# Course.net
KiCad netlist of a schematic drawn in Altium Designer
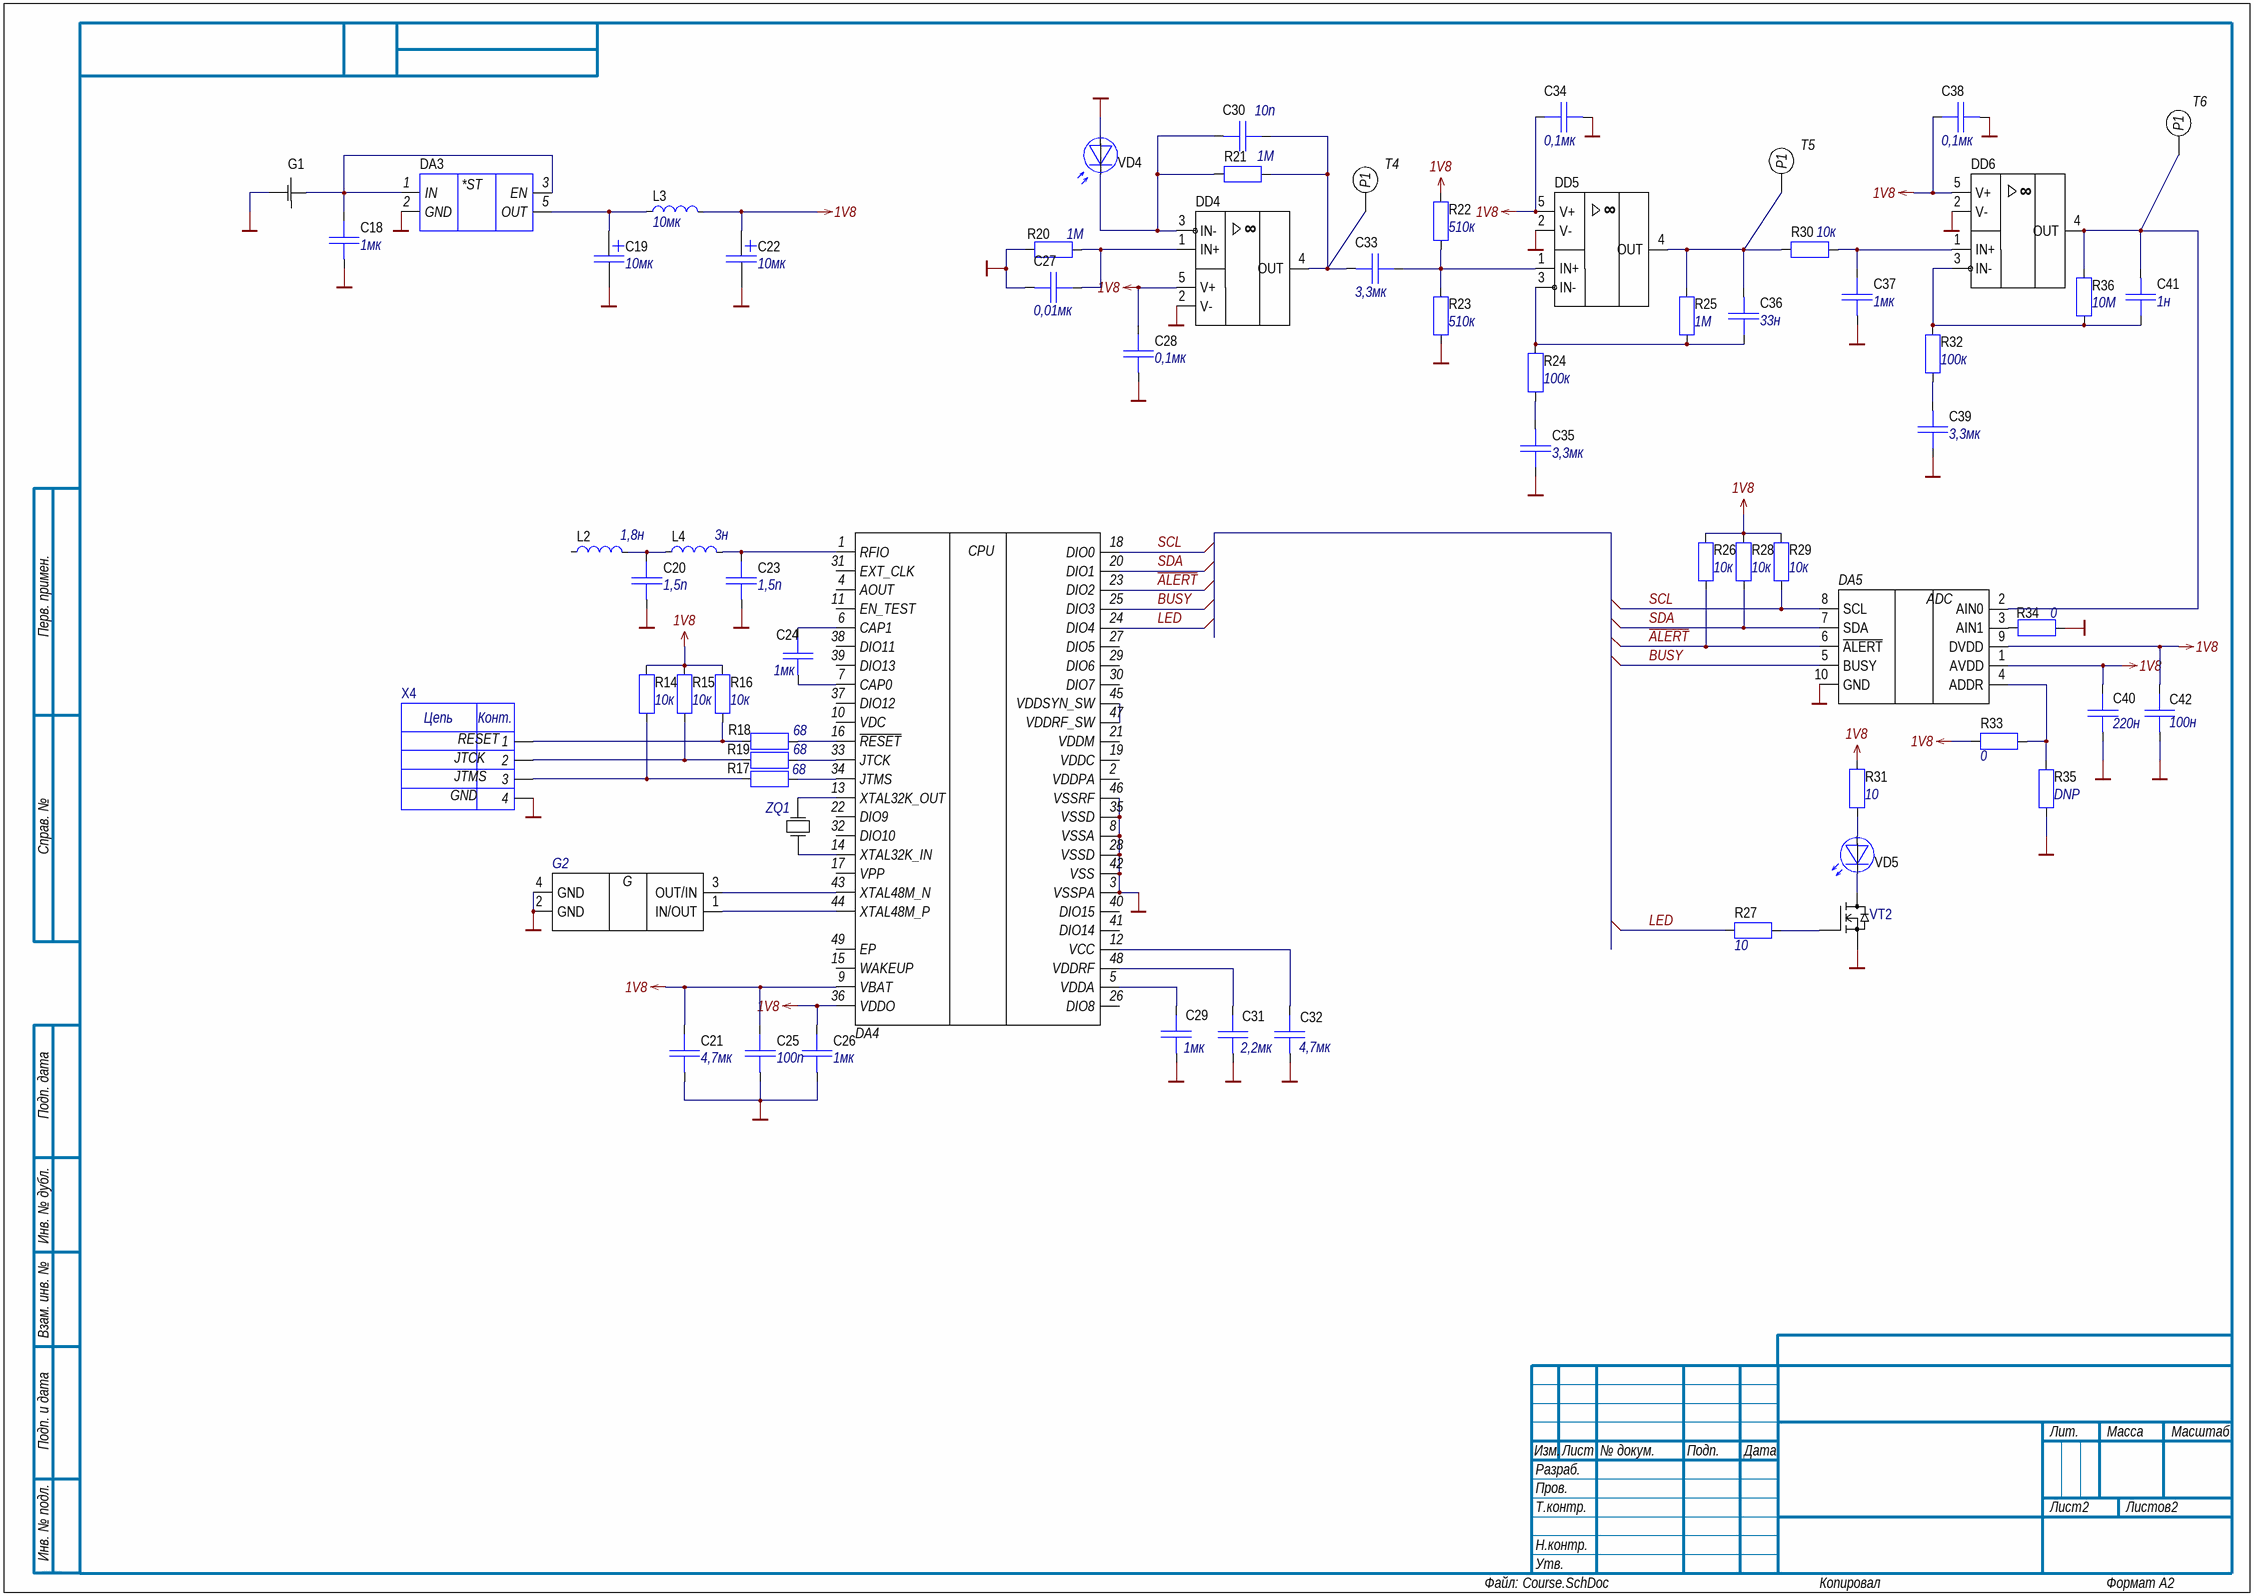
[diagram p0: Course.SchDoc]

(export (version "E")
  (design (tool "Eeschema 10.0.6"))
  (components
    (comp (ref "C18")
      (value "1мк")
      (footprint "cap0603")
      (description "Керамический конденсатор")
      (libsource (lib "RSL10_SchLib") (part "CapCer"))
    )
    (comp (ref "C19")
      (value "10мк")
      (description "Танталовый конденсатор")
      (libsource (lib "RSL10_SchLib") (part "CapTan"))
    )
    (comp (ref "C20")
      (value "1,5п")
      (footprint "cap0603")
      (description "Керамический конденсатор")
      (libsource (lib "RSL10_SchLib") (part "CapCer"))
    )
    (comp (ref "C21")
      (value "4,7мк")
      (footprint "CAP0805")
      (description "Керамический конденсатор")
      (libsource (lib "RSL10_SchLib") (part "CapCer"))
    )
    (comp (ref "C22")
      (value "10мк")
      (description "Танталовый конденсатор")
      (libsource (lib "RSL10_SchLib") (part "CapTan"))
    )
    (comp (ref "C23")
      (value "1,5п")
      (footprint "cap0603")
      (description "Керамический конденсатор")
      (libsource (lib "RSL10_SchLib") (part "CapCer"))
    )
    (comp (ref "C24")
      (value "1мк")
      (footprint "cap0603")
      (description "Керамический конденсатор")
      (libsource (lib "RSL10_SchLib") (part "CapCer"))
    )
    (comp (ref "C25")
      (value "100п")
      (footprint "cap0603")
      (description "Керамический конденсатор")
      (libsource (lib "RSL10_SchLib") (part "CapCer"))
    )
    (comp (ref "C26")
      (value "1мк")
      (footprint "cap0603")
      (description "Керамический конденсатор")
      (libsource (lib "RSL10_SchLib") (part "CapCer"))
    )
    (comp (ref "C27")
      (value "0,01мк")
      (footprint "cap0603")
      (description "Керамический конденсатор")
      (libsource (lib "RSL10_SchLib") (part "CapCer"))
    )
    (comp (ref "C28")
      (value "0,1мк")
      (footprint "cap0603")
      (description "Керамический конденсатор")
      (libsource (lib "RSL10_SchLib") (part "CapCer"))
    )
    (comp (ref "C29")
      (value "1мк")
      (footprint "cap0603")
      (description "Керамический конденсатор")
      (libsource (lib "RSL10_SchLib") (part "CapCer"))
    )
    (comp (ref "C30")
      (value "10п")
      (footprint "cap0603")
      (description "Керамический конденсатор")
      (libsource (lib "RSL10_SchLib") (part "CapCer"))
    )
    (comp (ref "C31")
      (value "2,2мк")
      (footprint "cap0603")
      (description "Керамический конденсатор")
      (libsource (lib "RSL10_SchLib") (part "CapCer"))
    )
    (comp (ref "C32")
      (value "4,7мк")
      (footprint "CAP0805")
      (description "Керамический конденсатор")
      (libsource (lib "RSL10_SchLib") (part "CapCer"))
    )
    (comp (ref "C33")
      (value "3,3мк")
      (footprint "CAP0805")
      (description "Керамический конденсатор")
      (libsource (lib "RSL10_SchLib") (part "CapCer"))
    )
    (comp (ref "C34")
      (value "0,1мк")
      (footprint "cap0603")
      (description "Керамический конденсатор")
      (libsource (lib "RSL10_SchLib") (part "CapCer"))
    )
    (comp (ref "C35")
      (value "3,3мк")
      (footprint "CAP0805")
      (description "Керамический конденсатор")
      (libsource (lib "RSL10_SchLib") (part "CapCer"))
    )
    (comp (ref "C36")
      (value "33н")
      (footprint "cap0603")
      (description "Керамический конденсатор")
      (libsource (lib "RSL10_SchLib") (part "CapCer"))
    )
    (comp (ref "C37")
      (value "1мк")
      (footprint "cap0603")
      (description "Керамический конденсатор")
      (libsource (lib "RSL10_SchLib") (part "CapCer"))
    )
    (comp (ref "C38")
      (value "0,1мк")
      (footprint "cap0603")
      (description "Керамический конденсатор")
      (libsource (lib "RSL10_SchLib") (part "CapCer"))
    )
    (comp (ref "C39")
      (value "3,3мк")
      (footprint "CAP0805")
      (description "Керамический конденсатор")
      (libsource (lib "RSL10_SchLib") (part "CapCer"))
    )
    (comp (ref "C40")
      (value "220н")
      (footprint "cap0603")
      (description "Керамический конденсатор")
      (libsource (lib "RSL10_SchLib") (part "CapCer"))
    )
    (comp (ref "C41")
      (value "1н")
      (footprint "cap0603")
      (description "Керамический конденсатор")
      (libsource (lib "RSL10_SchLib") (part "CapCer"))
    )
    (comp (ref "C42")
      (value "100н")
      (footprint "cap0603")
      (description "Керамический конденсатор")
      (libsource (lib "RSL10_SchLib") (part "CapCer"))
    )
    (comp (ref "DA3")
      (value "TPS7A0218PDBVR")
      (footprint "TPS7A02")
      (libsource (lib "RSL10_SchLib") (part "LDO"))
    )
    (comp (ref "DA4") (value "RSL10") (footprint "RSL10") (libsource (lib "RSL10_SchLib") (part "RSL10")))
    (comp (ref "DA5") (value "ADC") (footprint "ADS7142IRUGT") (libsource (lib "RSL10_SchLib") (part "ADC")))
    (comp (ref "DD4")
      (value "operational amplifier_2")
      (footprint "OPA333")
      (description "Операционный усилитель")
      (libsource (lib "RSL10_SchLib") (part "operational amplifier_2"))
    )
    (comp (ref "DD5")
      (value "operational amplifier_1")
      (footprint "OPA333")
      (description "Операционный усилитель")
      (libsource (lib "RSL10_SchLib") (part "operational amplifier_1"))
    )
    (comp (ref "DD6")
      (value "operational amplifier_1")
      (footprint "OPA333")
      (description "Операционный усилитель")
      (libsource (lib "RSL10_SchLib") (part "operational amplifier_1"))
    )
    (comp (ref "G1") (value "battery") (libsource (lib "RSL10_SchLib") (part "battery")))
    (comp (ref "G2")
      (value "Обозначение при заказе")
      (footprint "XTAL48")
      (description "ECS-480-8-47-JTN-TR")
      (libsource (lib "RSL10_SchLib") (part "XTAL48"))
    )
    (comp (ref "L2")
      (value "1,8н")
      (footprint "IND0402")
      (description "Катушка индуктивности")
      (libsource (lib "RSL10_SchLib") (part "Ind"))
    )
    (comp (ref "L3")
      (value "10мк")
      (footprint "MLZ1608M100WT000")
      (description "Катушка индуктивности")
      (libsource (lib "RSL10_SchLib") (part "Ind"))
    )
    (comp (ref "L4")
      (value "3н")
      (footprint "IND0402")
      (description "Катушка индуктивности")
      (libsource (lib "RSL10_SchLib") (part "Ind"))
    )
    (comp (ref "R14")
      (value "10к")
      (footprint "Res0603")
      (description "Резистор")
      (fields (field (name "TOLERANCE") "5%") (field (name "MANUFACTURER") "АЛЯР.434110.005ТУ"))
      (libsource (lib "") (part "Res_2"))
    )
    (comp (ref "R15")
      (value "10к")
      (footprint "Res0603")
      (description "Резистор")
      (fields (field (name "TOLERANCE") "5%") (field (name "MANUFACTURER") "АЛЯР.434110.005ТУ"))
      (libsource (lib "") (part "Res_2"))
    )
    (comp (ref "R16")
      (value "10к")
      (footprint "Res0603")
      (description "Резистор")
      (fields (field (name "TOLERANCE") "5%") (field (name "MANUFACTURER") "АЛЯР.434110.005ТУ"))
      (libsource (lib "") (part "Res_2"))
    )
    (comp (ref "R17")
      (value "68")
      (footprint "Res0603")
      (description "Резистор")
      (libsource (lib "") (part "Res_1"))
    )
    (comp (ref "R18")
      (value "68")
      (footprint "Res0603")
      (description "Резистор")
      (libsource (lib "") (part "Res_1"))
    )
    (comp (ref "R19")
      (value "68")
      (footprint "Res0603")
      (description "Резистор")
      (libsource (lib "") (part "Res_1"))
    )
    (comp (ref "R20")
      (value "1M")
      (footprint "Res0603")
      (description "Резистор")
      (fields (field (name "TOLERANCE") "1%"))
      (libsource (lib "RSL10_SchLib") (part "Res"))
    )
    (comp (ref "R21")
      (value "1M")
      (footprint "Res0603")
      (description "Резистор")
      (libsource (lib "RSL10_SchLib") (part "Res"))
    )
    (comp (ref "R22")
      (value "510к")
      (footprint "Res0603")
      (description "Резистор")
      (libsource (lib "") (part "Res_3"))
    )
    (comp (ref "R23")
      (value "510к")
      (footprint "Res0603")
      (description "Резистор")
      (libsource (lib "") (part "Res_3"))
    )
    (comp (ref "R24")
      (value "100к")
      (footprint "Res0603")
      (description "Резистор")
      (libsource (lib "") (part "Res_1"))
    )
    (comp (ref "R25")
      (value "1М")
      (footprint "Res0603")
      (description "Резистор")
      (fields (field (name "TOLERANCE") "1%"))
      (libsource (lib "") (part "Res_1"))
    )
    (comp (ref "R26")
      (value "10к")
      (footprint "Res0603")
      (description "Резистор")
      (fields (field (name "TOLERANCE") "5%") (field (name "MANUFACTURER") "АЛЯР.434110.005ТУ"))
      (libsource (lib "") (part "Res_2"))
    )
    (comp (ref "R27")
      (value "10")
      (footprint "Res0603")
      (description "Резистор")
      (fields (field (name "TOLERANCE") "5%"))
      (libsource (lib "") (part "Res_1"))
    )
    (comp (ref "R28")
      (value "10к")
      (footprint "Res0603")
      (description "Резистор")
      (fields (field (name "TOLERANCE") "5%") (field (name "MANUFACTURER") "АЛЯР.434110.005ТУ"))
      (libsource (lib "") (part "Res_2"))
    )
    (comp (ref "R29")
      (value "10к")
      (footprint "Res0603")
      (description "Резистор")
      (fields (field (name "TOLERANCE") "5%") (field (name "MANUFACTURER") "АЛЯР.434110.005ТУ"))
      (libsource (lib "") (part "Res_2"))
    )
    (comp (ref "R30")
      (value "10к")
      (footprint "Res0603")
      (description "Резистор")
      (fields (field (name "TOLERANCE") "5%") (field (name "MANUFACTURER") "АЛЯР.434110.005ТУ"))
      (libsource (lib "") (part "Res_1"))
    )
    (comp (ref "R31")
      (value "10")
      (footprint "Res0603")
      (description "Резистор")
      (fields (field (name "TOLERANCE") "5%"))
      (libsource (lib "RSL10_SchLib") (part "Res"))
    )
    (comp (ref "R32")
      (value "100к")
      (footprint "Res0603")
      (description "Резистор")
      (libsource (lib "") (part "Res_1"))
    )
    (comp (ref "R33")
      (value "0")
      (footprint "Res0603")
      (description "Резистор")
      (fields (field (name "TOLERANCE") "5%") (field (name "MANUFACTURER") "АЛЯР.434110.005ТУ"))
      (libsource (lib "RSL10_SchLib") (part "Res"))
    )
    (comp (ref "R34")
      (value "0")
      (footprint "Res0603")
      (description "Резистор")
      (fields (field (name "TOLERANCE") "5%") (field (name "MANUFACTURER") "АЛЯР.434110.005ТУ"))
      (libsource (lib "RSL10_SchLib") (part "Res"))
    )
    (comp (ref "R35")
      (value "DNP")
      (footprint "Res0603")
      (description "Резистор")
      (fields (field (name "TOLERANCE") "5%") (field (name "MANUFACTURER") "АЛЯР.434110.005ТУ"))
      (libsource (lib "") (part "Res_2"))
    )
    (comp (ref "R36")
      (value "10М")
      (footprint "Res0603")
      (description "Резистор")
      (libsource (lib "") (part "Res_1"))
    )
    (comp (ref "T4")
      (value "TestPoint")
      (footprint "TestPoint")
      (libsource (lib "RSL10_SchLib") (part "TestPoint"))
    )
    (comp (ref "T5")
      (value "TestPoint")
      (footprint "TestPoint")
      (libsource (lib "RSL10_SchLib") (part "TestPoint"))
    )
    (comp (ref "T6")
      (value "TestPoint")
      (footprint "TestPoint")
      (libsource (lib "RSL10_SchLib") (part "TestPoint"))
    )
    (comp (ref "VD4")
      (value "SFH 2703")
      (description "Photodiode")
      (libsource (lib "RSL10_SchLib") (part "Photodiode"))
    )
    (comp (ref "VD5")
      (value "15412094A9000аА0.339.189ТУ")
      (footprint "LED1206")
      (description "Излучатель")
      (libsource (lib "RSL10_SchLib") (part "Led"))
    )
    (comp (ref "VT2")
      (value "RU1J002YNTCL")
      (footprint "Mosfet")
      (description "N-MOSFET DirectFET SQ")
      (libsource (lib "RSL10_SchLib") (part "RU1J002YNTCL"))
    )
    (comp (ref "X4")
      (value "PLS-6БСАР.430420.014ТУ")
      (footprint "PSL_4")
      (libsource (lib "RSL10_SchLib") (part "PSL4"))
    )
    (comp (ref "ZQ1")
      (value "Обозначение при заказе")
      (footprint "XTAL32")
      (description "FC-135 32.7680KA-AG0")
      (libsource (lib "RSL10_SchLib") (part "XTAL32.768"))
    )
  )
  (nets
    (net (code "1") (name "/BUSY") (class "Default")
      (node (ref "DA4") (pin "25") (pinfunction "DIO3_25") (pintype "passive"))
      (node (ref "DA5") (pin "5") (pinfunction "BUSY_5") (pintype "passive"))
    )
    (net (code "2") (name "/LED") (class "Default")
      (node (ref "DA4") (pin "24") (pinfunction "DIO4_24") (pintype "passive"))
      (node (ref "R27") (pin "2") (pinfunction "2_2") (pintype "passive"))
    )
    (net (code "3") (name "/SCL") (class "Default")
      (node (ref "DA4") (pin "18") (pinfunction "DIO0_18") (pintype "passive"))
      (node (ref "DA5") (pin "8") (pinfunction "SCL_8") (pintype "passive"))
      (node (ref "R29") (pin "2") (pinfunction "2_2") (pintype "passive"))
    )
    (net (code "4") (name "/SDA") (class "Default")
      (node (ref "DA4") (pin "20") (pinfunction "DIO1_20") (pintype "passive"))
      (node (ref "DA5") (pin "7") (pinfunction "SDA_7") (pintype "passive"))
      (node (ref "R28") (pin "2") (pinfunction "2_2") (pintype "passive"))
    )
    (net (code "5") (name "/~{ALERT}") (class "Default")
      (node (ref "DA4") (pin "23") (pinfunction "DIO2_23") (pintype "passive"))
      (node (ref "DA5") (pin "6") (pinfunction "~{ALERT}_6") (pintype "passive"))
      (node (ref "R26") (pin "2") (pinfunction "2_2") (pintype "passive"))
    )
    (net (code "6") (name "1V8") (class "Default")
      (node (ref "C21") (pin "2") (pinfunction "2_2") (pintype "passive"))
      (node (ref "C22") (pin "1") (pinfunction "1_1") (pintype "passive"))
      (node (ref "C25") (pin "2") (pinfunction "2_2") (pintype "passive"))
      (node (ref "C26") (pin "2") (pinfunction "2_2") (pintype "passive"))
      (node (ref "C28") (pin "2") (pinfunction "2_2") (pintype "passive"))
      (node (ref "C34") (pin "2") (pinfunction "2_2") (pintype "passive"))
      (node (ref "C38") (pin "2") (pinfunction "2_2") (pintype "passive"))
      (node (ref "C40") (pin "2") (pinfunction "2_2") (pintype "passive"))
      (node (ref "C42") (pin "2") (pinfunction "2_2") (pintype "passive"))
      (node (ref "DA4") (pin "36") (pinfunction "VDDO_36") (pintype "passive"))
      (node (ref "DA4") (pin "9") (pinfunction "VBAT_9") (pintype "passive"))
      (node (ref "DA5") (pin "1") (pinfunction "AVDD_1") (pintype "passive"))
      (node (ref "DA5") (pin "9") (pinfunction "DVDD_9") (pintype "passive"))
      (node (ref "DD4") (pin "5") (pinfunction "V+_5") (pintype "passive"))
      (node (ref "DD5") (pin "5") (pinfunction "V+_5") (pintype "passive"))
      (node (ref "DD6") (pin "5") (pinfunction "V+_5") (pintype "passive"))
      (node (ref "L3") (pin "2") (pinfunction "2_2") (pintype "passive"))
      (node (ref "R14") (pin "1") (pinfunction "1_1") (pintype "passive"))
      (node (ref "R15") (pin "1") (pinfunction "1_1") (pintype "passive"))
      (node (ref "R16") (pin "1") (pinfunction "1_1") (pintype "passive"))
      (node (ref "R22") (pin "2") (pinfunction "2_2") (pintype "passive"))
      (node (ref "R26") (pin "1") (pinfunction "1_1") (pintype "passive"))
      (node (ref "R28") (pin "1") (pinfunction "1_1") (pintype "passive"))
      (node (ref "R29") (pin "1") (pinfunction "1_1") (pintype "passive"))
      (node (ref "R31") (pin "2") (pinfunction "2_2") (pintype "passive"))
      (node (ref "R33") (pin "1") (pinfunction "1_1") (pintype "passive"))
    )
    (net (code "7") (name "GND") (class "Default")
      (node (ref "C18") (pin "1") (pinfunction "1_1") (pintype "passive"))
      (node (ref "C19") (pin "2") (pinfunction "2_2") (pintype "passive"))
      (node (ref "C20") (pin "1") (pinfunction "1_1") (pintype "passive"))
      (node (ref "C21") (pin "1") (pinfunction "1_1") (pintype "passive"))
      (node (ref "C22") (pin "2") (pinfunction "2_2") (pintype "passive"))
      (node (ref "C23") (pin "1") (pinfunction "1_1") (pintype "passive"))
      (node (ref "C25") (pin "1") (pinfunction "1_1") (pintype "passive"))
      (node (ref "C26") (pin "1") (pinfunction "1_1") (pintype "passive"))
      (node (ref "C27") (pin "1") (pinfunction "1_1") (pintype "passive"))
      (node (ref "C28") (pin "1") (pinfunction "1_1") (pintype "passive"))
      (node (ref "C29") (pin "1") (pinfunction "1_1") (pintype "passive"))
      (node (ref "C31") (pin "1") (pinfunction "1_1") (pintype "passive"))
      (node (ref "C32") (pin "1") (pinfunction "1_1") (pintype "passive"))
      (node (ref "C34") (pin "1") (pinfunction "1_1") (pintype "passive"))
      (node (ref "C35") (pin "2") (pinfunction "2_2") (pintype "passive"))
      (node (ref "C37") (pin "1") (pinfunction "1_1") (pintype "passive"))
      (node (ref "C38") (pin "1") (pinfunction "1_1") (pintype "passive"))
      (node (ref "C39") (pin "2") (pinfunction "2_2") (pintype "passive"))
      (node (ref "C40") (pin "1") (pinfunction "1_1") (pintype "passive"))
      (node (ref "C42") (pin "1") (pinfunction "1_1") (pintype "passive"))
      (node (ref "DA3") (pin "2") (pinfunction "GND_2") (pintype "passive"))
      (node (ref "DA4") (pin "28") (pinfunction "VSSD_28") (pintype "passive"))
      (node (ref "DA4") (pin "3") (pinfunction "VSSPA_3") (pintype "passive"))
      (node (ref "DA4") (pin "35") (pinfunction "VSSD_35") (pintype "passive"))
      (node (ref "DA4") (pin "42") (pinfunction "VSS_42") (pintype "passive"))
      (node (ref "DA4") (pin "46") (pinfunction "VSSRF_46") (pintype "passive"))
      (node (ref "DA4") (pin "8") (pinfunction "VSSA_8") (pintype "passive"))
      (node (ref "DA5") (pin "10") (pinfunction "GND_10") (pintype "passive"))
      (node (ref "DD4") (pin "2") (pinfunction "V-_2") (pintype "passive"))
      (node (ref "DD5") (pin "2") (pinfunction "V-_2") (pintype "passive"))
      (node (ref "DD6") (pin "2") (pinfunction "V-_2") (pintype "passive"))
      (node (ref "G1") (pin "-") (pinfunction "-_-") (pintype "passive"))
      (node (ref "G2") (pin "2") (pinfunction "GND_2") (pintype "passive"))
      (node (ref "G2") (pin "4") (pinfunction "GND_4") (pintype "passive"))
      (node (ref "R20") (pin "1") (pinfunction "1_1") (pintype "passive"))
      (node (ref "R23") (pin "1") (pinfunction "1_1") (pintype "passive"))
      (node (ref "R34") (pin "2") (pinfunction "2_2") (pintype "passive"))
      (node (ref "R35") (pin "2") (pinfunction "2_2") (pintype "passive"))
      (node (ref "VD4") (pin "1") (pinfunction "1_1") (pintype "passive"))
      (node (ref "VT2") (pin "2") (pinfunction "S_2") (pintype "power_in"))
      (node (ref "X4") (pin "4") (pinfunction "4_4") (pintype "passive"))
    )
    (net (code "8") (name "Net-(C20-Pad2)") (class "Default")
      (node (ref "C20") (pin "2") (pinfunction "2_2") (pintype "passive"))
      (node (ref "L2") (pin "2") (pinfunction "2_2") (pintype "passive"))
      (node (ref "L4") (pin "1") (pinfunction "1_1") (pintype "passive"))
    )
    (net (code "9") (name "Net-(C35-Pad1)") (class "Default")
      (node (ref "C35") (pin "1") (pinfunction "1_1") (pintype "passive"))
      (node (ref "R24") (pin "2") (pinfunction "2_2") (pintype "passive"))
    )
    (net (code "10") (name "Net-(C39-Pad1)") (class "Default")
      (node (ref "C39") (pin "1") (pinfunction "1_1") (pintype "passive"))
      (node (ref "R32") (pin "2") (pinfunction "2_2") (pintype "passive"))
    )
    (net (code "11") (name "Net-(DA3-EN)") (class "Default")
      (node (ref "C18") (pin "2") (pinfunction "2_2") (pintype "passive"))
      (node (ref "DA3") (pin "1") (pinfunction "IN_1") (pintype "passive"))
      (node (ref "DA3") (pin "3") (pinfunction "EN_3") (pintype "passive"))
      (node (ref "G1") (pin "+") (pinfunction "+_+") (pintype "passive"))
    )
    (net (code "12") (name "Net-(DA3-OUT)") (class "Default")
      (node (ref "C19") (pin "1") (pinfunction "1_1") (pintype "passive"))
      (node (ref "DA3") (pin "5") (pinfunction "OUT_5") (pintype "passive"))
      (node (ref "L3") (pin "1") (pinfunction "1_1") (pintype "passive"))
    )
    (net (code "13") (name "Net-(DA4-CAP0)") (class "Default")
      (node (ref "C24") (pin "1") (pinfunction "1_1") (pintype "passive"))
      (node (ref "DA4") (pin "7") (pinfunction "CAP0_7") (pintype "passive"))
    )
    (net (code "14") (name "Net-(DA4-CAP1)") (class "Default")
      (node (ref "C24") (pin "2") (pinfunction "2_2") (pintype "passive"))
      (node (ref "DA4") (pin "6") (pinfunction "CAP1_6") (pintype "passive"))
    )
    (net (code "15") (name "Net-(DA4-JTCK)") (class "Default")
      (node (ref "DA4") (pin "33") (pinfunction "JTCK_33") (pintype "passive"))
      (node (ref "R19") (pin "1") (pinfunction "1_1") (pintype "passive"))
    )
    (net (code "16") (name "Net-(DA4-JTMS)") (class "Default")
      (node (ref "DA4") (pin "34") (pinfunction "JTMS_34") (pintype "passive"))
      (node (ref "R17") (pin "1") (pinfunction "1_1") (pintype "passive"))
    )
    (net (code "17") (name "Net-(DA4-RESET)") (class "Default")
      (node (ref "DA4") (pin "16") (pinfunction "RESET_16") (pintype "passive"))
      (node (ref "R18") (pin "1") (pinfunction "1_1") (pintype "passive"))
    )
    (net (code "18") (name "Net-(DA4-RFIO)") (class "Default")
      (node (ref "C23") (pin "2") (pinfunction "2_2") (pintype "passive"))
      (node (ref "DA4") (pin "1") (pinfunction "RFIO_1") (pintype "passive"))
      (node (ref "L4") (pin "2") (pinfunction "2_2") (pintype "passive"))
    )
    (net (code "19") (name "Net-(DA4-VCC)") (class "Default")
      (node (ref "C32") (pin "2") (pinfunction "2_2") (pintype "passive"))
      (node (ref "DA4") (pin "12") (pinfunction "VCC_12") (pintype "passive"))
    )
    (net (code "20") (name "Net-(DA4-VDDA)") (class "Default")
      (node (ref "C29") (pin "2") (pinfunction "2_2") (pintype "passive"))
      (node (ref "DA4") (pin "5") (pinfunction "VDDA_5") (pintype "passive"))
    )
    (net (code "21") (name "Net-(DA4-VDDRF)") (class "Default")
      (node (ref "C31") (pin "2") (pinfunction "2_2") (pintype "passive"))
      (node (ref "DA4") (pin "48") (pinfunction "VDDRF_48") (pintype "passive"))
    )
    (net (code "22") (name "Net-(DA4-VDDRF_SW)") (class "Default")
      (node (ref "DA4") (pin "45") (pinfunction "VDDSYN_SW_45") (pintype "passive"))
      (node (ref "DA4") (pin "47") (pinfunction "VDDRF_SW_47") (pintype "passive"))
    )
    (net (code "23") (name "Net-(DA4-XTAL32K_IN)") (class "Default")
      (node (ref "DA4") (pin "14") (pinfunction "XTAL32K_IN_14") (pintype "passive"))
      (node (ref "ZQ1") (pin "1") (pinfunction "1_1") (pintype "passive"))
    )
    (net (code "24") (name "Net-(DA4-XTAL32K_OUT)") (class "Default")
      (node (ref "DA4") (pin "13") (pinfunction "XTAL32K_OUT_13") (pintype "passive"))
      (node (ref "ZQ1") (pin "2") (pinfunction "2_2") (pintype "passive"))
    )
    (net (code "25") (name "Net-(DA4-XTAL48M_N)") (class "Default")
      (node (ref "DA4") (pin "43") (pinfunction "XTAL48M_N_43") (pintype "passive"))
      (node (ref "G2") (pin "3") (pinfunction "OUT/IN_3") (pintype "passive"))
    )
    (net (code "26") (name "Net-(DA4-XTAL48M_P)") (class "Default")
      (node (ref "DA4") (pin "44") (pinfunction "XTAL48M_P_44") (pintype "passive"))
      (node (ref "G2") (pin "1") (pinfunction "IN/OUT_1") (pintype "passive"))
    )
    (net (code "27") (name "Net-(DA5-ADDR)") (class "Default")
      (node (ref "DA5") (pin "4") (pinfunction "ADDR_4") (pintype "passive"))
      (node (ref "R33") (pin "2") (pinfunction "2_2") (pintype "passive"))
      (node (ref "R35") (pin "1") (pinfunction "1_1") (pintype "passive"))
    )
    (net (code "28") (name "Net-(DA5-AIN0)") (class "Default")
      (node (ref "C41") (pin "1") (pinfunction "1_1") (pintype "passive"))
      (node (ref "DA5") (pin "2") (pinfunction "AIN0_2") (pintype "passive"))
      (node (ref "DD6") (pin "4") (pinfunction "OUT_4") (pintype "passive"))
      (node (ref "R36") (pin "1") (pinfunction "1_1") (pintype "passive"))
      (node (ref "T6") (pin "T") (pinfunction "P1_T") (pintype "passive"))
    )
    (net (code "29") (name "Net-(DA5-AIN1)") (class "Default")
      (node (ref "DA5") (pin "3") (pinfunction "AIN1_3") (pintype "passive"))
      (node (ref "R34") (pin "1") (pinfunction "1_1") (pintype "passive"))
    )
    (net (code "30") (name "Net-(DD4-IN+)") (class "Default")
      (node (ref "C27") (pin "2") (pinfunction "2_2") (pintype "passive"))
      (node (ref "DD4") (pin "1") (pinfunction "IN+_1") (pintype "passive"))
      (node (ref "R20") (pin "2") (pinfunction "2_2") (pintype "passive"))
    )
    (net (code "31") (name "Net-(DD4-IN-)") (class "Default")
      (node (ref "C30") (pin "1") (pinfunction "1_1") (pintype "passive"))
      (node (ref "DD4") (pin "3") (pinfunction "IN-_3") (pintype "passive"))
      (node (ref "R21") (pin "1") (pinfunction "1_1") (pintype "passive"))
      (node (ref "VD4") (pin "2") (pinfunction "2_2") (pintype "passive"))
    )
    (net (code "32") (name "Net-(DD4-OUT)") (class "Default")
      (node (ref "C30") (pin "2") (pinfunction "2_2") (pintype "passive"))
      (node (ref "C33") (pin "1") (pinfunction "1_1") (pintype "passive"))
      (node (ref "DD4") (pin "4") (pinfunction "OUT_4") (pintype "passive"))
      (node (ref "R21") (pin "2") (pinfunction "2_2") (pintype "passive"))
      (node (ref "T4") (pin "T") (pinfunction "P1_T") (pintype "passive"))
    )
    (net (code "33") (name "Net-(DD5-IN+)") (class "Default")
      (node (ref "C33") (pin "2") (pinfunction "2_2") (pintype "passive"))
      (node (ref "DD5") (pin "1") (pinfunction "IN+_1") (pintype "passive"))
      (node (ref "R22") (pin "1") (pinfunction "1_1") (pintype "passive"))
      (node (ref "R23") (pin "2") (pinfunction "2_2") (pintype "passive"))
    )
    (net (code "34") (name "Net-(DD5-IN-)") (class "Default")
      (node (ref "C36") (pin "2") (pinfunction "2_2") (pintype "passive"))
      (node (ref "DD5") (pin "3") (pinfunction "IN-_3") (pintype "passive"))
      (node (ref "R24") (pin "1") (pinfunction "1_1") (pintype "passive"))
      (node (ref "R25") (pin "2") (pinfunction "2_2") (pintype "passive"))
    )
    (net (code "35") (name "Net-(DD5-OUT)") (class "Default")
      (node (ref "C36") (pin "1") (pinfunction "1_1") (pintype "passive"))
      (node (ref "DD5") (pin "4") (pinfunction "OUT_4") (pintype "passive"))
      (node (ref "R25") (pin "1") (pinfunction "1_1") (pintype "passive"))
      (node (ref "R30") (pin "2") (pinfunction "2_2") (pintype "passive"))
      (node (ref "T5") (pin "T") (pinfunction "P1_T") (pintype "passive"))
    )
    (net (code "36") (name "Net-(DD6-IN+)") (class "Default")
      (node (ref "C37") (pin "2") (pinfunction "2_2") (pintype "passive"))
      (node (ref "DD6") (pin "1") (pinfunction "IN+_1") (pintype "passive"))
      (node (ref "R30") (pin "1") (pinfunction "1_1") (pintype "passive"))
    )
    (net (code "37") (name "Net-(DD6-IN-)") (class "Default")
      (node (ref "C41") (pin "2") (pinfunction "2_2") (pintype "passive"))
      (node (ref "DD6") (pin "3") (pinfunction "IN-_3") (pintype "passive"))
      (node (ref "R32") (pin "1") (pinfunction "1_1") (pintype "passive"))
      (node (ref "R36") (pin "2") (pinfunction "2_2") (pintype "passive"))
    )
    (net (code "38") (name "Net-(R14-Pad2)") (class "Default")
      (node (ref "R14") (pin "2") (pinfunction "2_2") (pintype "passive"))
      (node (ref "R17") (pin "2") (pinfunction "2_2") (pintype "passive"))
      (node (ref "X4") (pin "3") (pinfunction "3_3") (pintype "passive"))
    )
    (net (code "39") (name "Net-(R15-Pad2)") (class "Default")
      (node (ref "R15") (pin "2") (pinfunction "2_2") (pintype "passive"))
      (node (ref "R19") (pin "2") (pinfunction "2_2") (pintype "passive"))
      (node (ref "X4") (pin "2") (pinfunction "2_2") (pintype "passive"))
    )
    (net (code "40") (name "Net-(R16-Pad2)") (class "Default")
      (node (ref "R16") (pin "2") (pinfunction "2_2") (pintype "passive"))
      (node (ref "R18") (pin "2") (pinfunction "2_2") (pintype "passive"))
      (node (ref "X4") (pin "1") (pinfunction "1_1") (pintype "passive"))
    )
    (net (code "41") (name "Net-(R31-Pad1)") (class "Default")
      (node (ref "R31") (pin "1") (pinfunction "1_1") (pintype "passive"))
      (node (ref "VD5") (pin "A") (pinfunction "A_A") (pintype "passive"))
    )
    (net (code "42") (name "Net-(VT2-D)") (class "Default")
      (node (ref "VD5") (pin "K") (pinfunction "K_K") (pintype "passive"))
      (node (ref "VT2") (pin "3") (pinfunction "D_3") (pintype "power_in"))
    )
    (net (code "43") (name "Net-(VT2-G)") (class "Default")
      (node (ref "R27") (pin "1") (pinfunction "1_1") (pintype "passive"))
      (node (ref "VT2") (pin "1") (pinfunction "G_1") (pintype "power_in"))
    )
    (net (code "44") (name "unconnected-(DA4-AOUT-Pad4)") (class "Default")
      (node (ref "DA4") (pin "4") (pinfunction "AOUT_4") (pintype "passive"))
    )
    (net (code "45") (name "unconnected-(DA4-DIO5-Pad27)") (class "Default")
      (node (ref "DA4") (pin "27") (pinfunction "DIO5_27") (pintype "passive"))
    )
    (net (code "46") (name "unconnected-(DA4-DIO6-Pad29)") (class "Default")
      (node (ref "DA4") (pin "29") (pinfunction "DIO6_29") (pintype "passive"))
    )
    (net (code "47") (name "unconnected-(DA4-DIO7-Pad30)") (class "Default")
      (node (ref "DA4") (pin "30") (pinfunction "DIO7_30") (pintype "passive"))
    )
    (net (code "48") (name "unconnected-(DA4-DIO8-Pad26)") (class "Default")
      (node (ref "DA4") (pin "26") (pinfunction "DIO8_26") (pintype "passive"))
    )
    (net (code "49") (name "unconnected-(DA4-DIO9-Pad22)") (class "Default")
      (node (ref "DA4") (pin "22") (pinfunction "DIO9_22") (pintype "passive"))
    )
    (net (code "50") (name "unconnected-(DA4-DIO10-Pad32)") (class "Default")
      (node (ref "DA4") (pin "32") (pinfunction "DIO10_32") (pintype "passive"))
    )
    (net (code "51") (name "unconnected-(DA4-DIO11-Pad38)") (class "Default")
      (node (ref "DA4") (pin "38") (pinfunction "DIO11_38") (pintype "passive"))
    )
    (net (code "52") (name "unconnected-(DA4-DIO12-Pad37)") (class "Default")
      (node (ref "DA4") (pin "37") (pinfunction "DIO12_37") (pintype "passive"))
    )
    (net (code "53") (name "unconnected-(DA4-DIO13-Pad39)") (class "Default")
      (node (ref "DA4") (pin "39") (pinfunction "DIO13_39") (pintype "passive"))
    )
    (net (code "54") (name "unconnected-(DA4-DIO14-Pad41)") (class "Default")
      (node (ref "DA4") (pin "41") (pinfunction "DIO14_41") (pintype "passive"))
    )
    (net (code "55") (name "unconnected-(DA4-DIO15-Pad40)") (class "Default")
      (node (ref "DA4") (pin "40") (pinfunction "DIO15_40") (pintype "passive"))
    )
    (net (code "56") (name "unconnected-(DA4-EN_TEST-Pad11)") (class "Default")
      (node (ref "DA4") (pin "11") (pinfunction "EN_TEST_11") (pintype "passive"))
    )
    (net (code "57") (name "unconnected-(DA4-EP-Pad49)") (class "Default")
      (node (ref "DA4") (pin "49") (pinfunction "EP_49") (pintype "passive"))
    )
    (net (code "58") (name "unconnected-(DA4-EXT_CLK-Pad31)") (class "Default")
      (node (ref "DA4") (pin "31") (pinfunction "EXT_CLK_31") (pintype "passive"))
    )
    (net (code "59") (name "unconnected-(DA4-VDC-Pad10)") (class "Default")
      (node (ref "DA4") (pin "10") (pinfunction "VDC_10") (pintype "passive"))
    )
    (net (code "60") (name "unconnected-(DA4-VDDC-Pad19)") (class "Default")
      (node (ref "DA4") (pin "19") (pinfunction "VDDC_19") (pintype "passive"))
    )
    (net (code "61") (name "unconnected-(DA4-VDDM-Pad21)") (class "Default")
      (node (ref "DA4") (pin "21") (pinfunction "VDDM_21") (pintype "passive"))
    )
    (net (code "62") (name "unconnected-(DA4-VDDPA-Pad2)") (class "Default")
      (node (ref "DA4") (pin "2") (pinfunction "VDDPA_2") (pintype "passive"))
    )
    (net (code "63") (name "unconnected-(DA4-VPP-Pad17)") (class "Default")
      (node (ref "DA4") (pin "17") (pinfunction "VPP_17") (pintype "passive"))
    )
    (net (code "64") (name "unconnected-(DA4-WAKEUP-Pad15)") (class "Default")
      (node (ref "DA4") (pin "15") (pinfunction "WAKEUP_15") (pintype "passive"))
    )
    (net (code "65") (name "unconnected-(L2-Pad1)") (class "Default")
      (node (ref "L2") (pin "1") (pinfunction "1_1") (pintype "passive"))
    )
  )
)
